# circuit.net
KiCad netlist of a schematic drawn in EAGLE
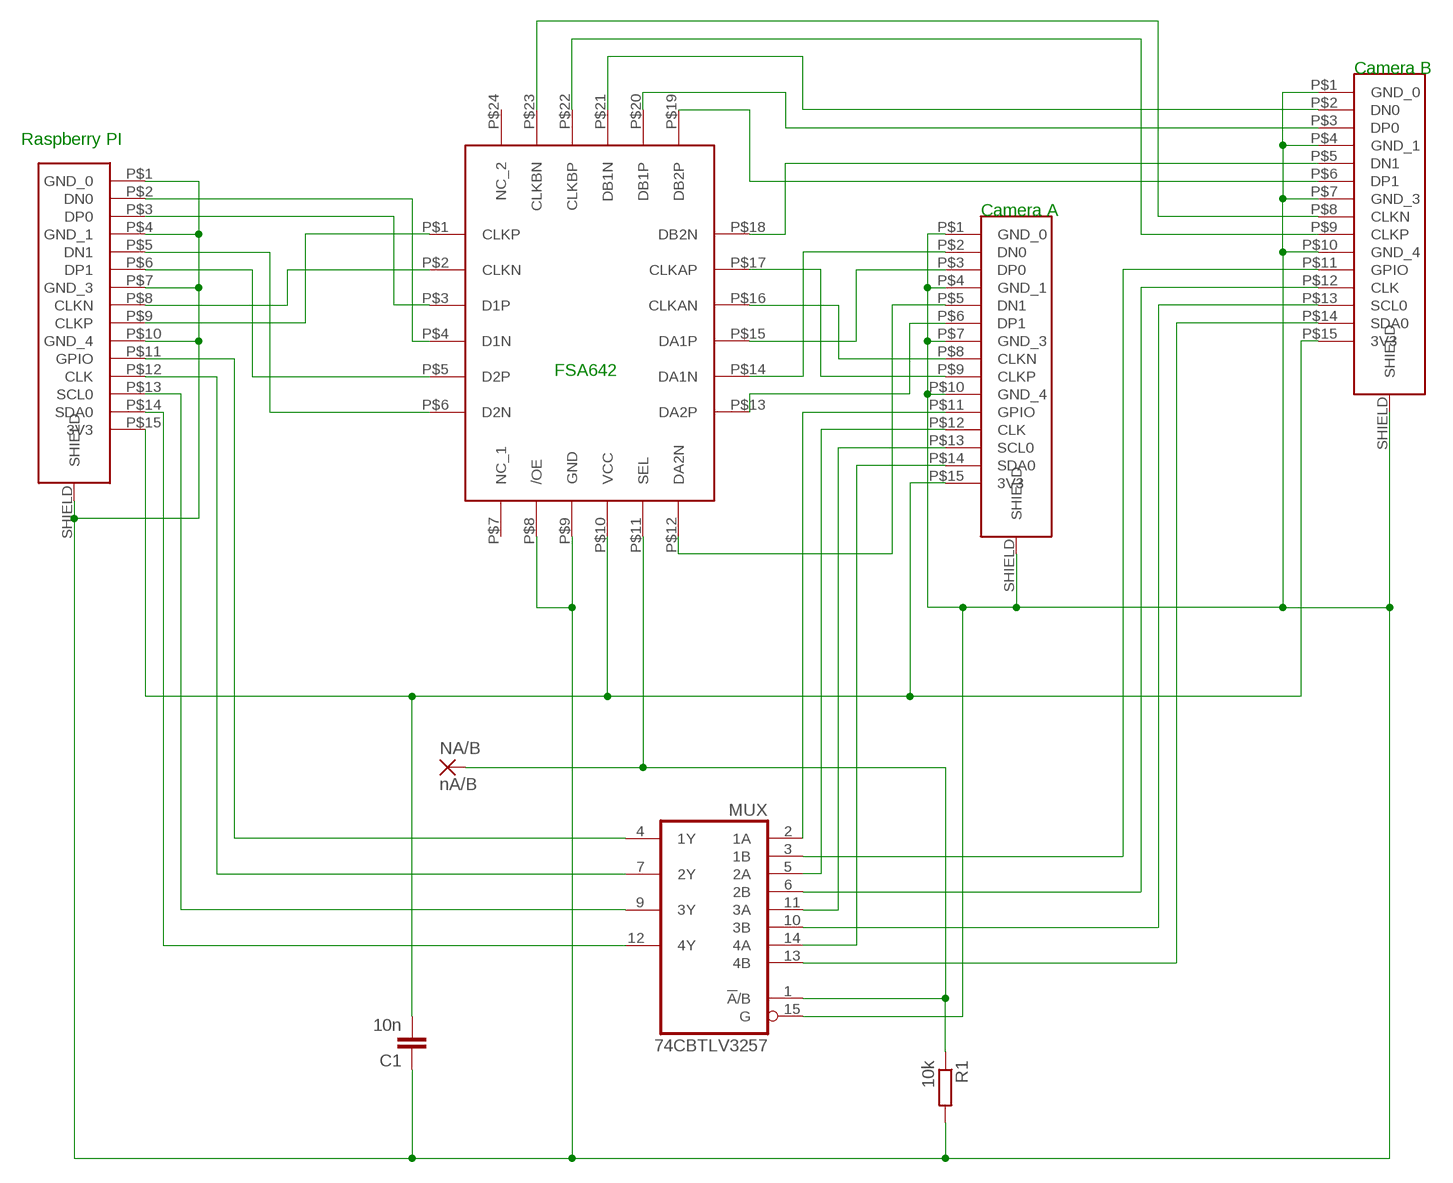
[diagram p0: schematic, sheet 1]

(export (version "E")
  (design (tool "Eeschema 10.0.6"))
  (components
    (comp (ref "C1")
      (value "10n")
      (footprint "eagle-import:C1206")
      (libsource (lib "eagle-import") (part "C-EUC1206"))
    )
    (comp (ref "CAM_A")
      (value "PICAM")
      (footprint "eagle-import:FPC-CONN-15-SMD")
      (libsource (lib "eagle-import") (part "PICAM"))
    )
    (comp (ref "CAM_B")
      (value "PICAM")
      (footprint "eagle-import:FPC-CONN-15-SMD")
      (libsource (lib "eagle-import") (part "PICAM"))
    )
    (comp (ref "MUX")
      (value "74CBTLV3257")
      (footprint "eagle-import:SO16")
      (libsource (lib "eagle-import") (part "74157DHCT"))
    )
    (comp (ref "NA/B")
      (value "nA/B")
      (footprint "eagle-import:SMD1,27-2,54")
      (libsource (lib "eagle-import") (part "SMD2"))
    )
    (comp (ref "R1")
      (value "10k")
      (footprint "eagle-import:R1206")
      (libsource (lib "eagle-import") (part "R-EU_R1206"))
    )
    (comp (ref "RPI")
      (value "PICAM")
      (footprint "eagle-import:FPC-CONN-15-SMD")
      (libsource (lib "eagle-import") (part "PICAM"))
    )
    (comp (ref "U$1")
      (value "FSA642")
      (footprint "eagle-import:UMLP-24")
      (libsource (lib "eagle-import") (part "FSA642"))
    )
  )
  (nets
    (net (code "1") (name "Net-(CAM_A-3V3)") (class "Default")
      (node (ref "C1") (pin "2") (pinfunction "2_2") (pintype "passive"))
      (node (ref "CAM_A") (pin "P$15") (pinfunction "3V3_P$15") (pintype "bidirectional"))
      (node (ref "CAM_B") (pin "P$15") (pinfunction "3V3_P$15") (pintype "bidirectional"))
      (node (ref "RPI") (pin "P$15") (pinfunction "3V3_P$15") (pintype "bidirectional"))
      (node (ref "U$1") (pin "P$10") (pinfunction "VCC_P$10") (pintype "bidirectional"))
    )
    (net (code "2") (name "Net-(CAM_A-CLK)") (class "Default")
      (node (ref "CAM_A") (pin "P$12") (pinfunction "CLK_P$12") (pintype "bidirectional"))
      (node (ref "MUX") (pin "5") (pinfunction "2A_5") (pintype "input"))
    )
    (net (code "3") (name "Net-(CAM_A-CLKN)") (class "Default")
      (node (ref "CAM_A") (pin "P$8") (pinfunction "CLKN_P$8") (pintype "bidirectional"))
      (node (ref "U$1") (pin "P$16") (pinfunction "CLKAN_P$16") (pintype "bidirectional"))
    )
    (net (code "4") (name "Net-(CAM_A-CLKP)") (class "Default")
      (node (ref "CAM_A") (pin "P$9") (pinfunction "CLKP_P$9") (pintype "bidirectional"))
      (node (ref "U$1") (pin "P$17") (pinfunction "CLKAP_P$17") (pintype "bidirectional"))
    )
    (net (code "5") (name "Net-(CAM_A-DN0)") (class "Default")
      (node (ref "CAM_A") (pin "P$2") (pinfunction "DN0_P$2") (pintype "bidirectional"))
      (node (ref "U$1") (pin "P$14") (pinfunction "DA1N_P$14") (pintype "bidirectional"))
    )
    (net (code "6") (name "Net-(CAM_A-DN1)") (class "Default")
      (node (ref "CAM_A") (pin "P$5") (pinfunction "DN1_P$5") (pintype "bidirectional"))
      (node (ref "U$1") (pin "P$12") (pinfunction "DA2N_P$12") (pintype "bidirectional"))
    )
    (net (code "7") (name "Net-(CAM_A-DP0)") (class "Default")
      (node (ref "CAM_A") (pin "P$3") (pinfunction "DP0_P$3") (pintype "bidirectional"))
      (node (ref "U$1") (pin "P$15") (pinfunction "DA1P_P$15") (pintype "bidirectional"))
    )
    (net (code "8") (name "Net-(CAM_A-DP1)") (class "Default")
      (node (ref "CAM_A") (pin "P$6") (pinfunction "DP1_P$6") (pintype "bidirectional"))
      (node (ref "U$1") (pin "P$13") (pinfunction "DA2P_P$13") (pintype "bidirectional"))
    )
    (net (code "9") (name "Net-(CAM_A-GND_0)") (class "Default")
      (node (ref "C1") (pin "1") (pinfunction "1_1") (pintype "passive"))
      (node (ref "CAM_A") (pin "P$1") (pinfunction "GND_0_P$1") (pintype "bidirectional"))
      (node (ref "CAM_A") (pin "P$10") (pinfunction "GND_4_P$10") (pintype "bidirectional"))
      (node (ref "CAM_A") (pin "P$4") (pinfunction "GND_1_P$4") (pintype "bidirectional"))
      (node (ref "CAM_A") (pin "P$7") (pinfunction "GND_3_P$7") (pintype "bidirectional"))
      (node (ref "CAM_A") (pin "SHIELD") (pinfunction "SHIELD_SHIELD") (pintype "bidirectional"))
      (node (ref "CAM_B") (pin "P$1") (pinfunction "GND_0_P$1") (pintype "bidirectional"))
      (node (ref "CAM_B") (pin "P$10") (pinfunction "GND_4_P$10") (pintype "bidirectional"))
      (node (ref "CAM_B") (pin "P$4") (pinfunction "GND_1_P$4") (pintype "bidirectional"))
      (node (ref "CAM_B") (pin "P$7") (pinfunction "GND_3_P$7") (pintype "bidirectional"))
      (node (ref "CAM_B") (pin "SHIELD") (pinfunction "SHIELD_SHIELD") (pintype "bidirectional"))
      (node (ref "MUX") (pin "15") (pinfunction "G_15") (pintype "input"))
      (node (ref "R1") (pin "2") (pinfunction "2_2") (pintype "passive"))
      (node (ref "RPI") (pin "P$1") (pinfunction "GND_0_P$1") (pintype "bidirectional"))
      (node (ref "RPI") (pin "P$10") (pinfunction "GND_4_P$10") (pintype "bidirectional"))
      (node (ref "RPI") (pin "P$4") (pinfunction "GND_1_P$4") (pintype "bidirectional"))
      (node (ref "RPI") (pin "P$7") (pinfunction "GND_3_P$7") (pintype "bidirectional"))
      (node (ref "RPI") (pin "SHIELD") (pinfunction "SHIELD_SHIELD") (pintype "bidirectional"))
      (node (ref "U$1") (pin "P$8") (pinfunction "/OE_P$8") (pintype "bidirectional"))
      (node (ref "U$1") (pin "P$9") (pinfunction "GND_P$9") (pintype "bidirectional"))
    )
    (net (code "10") (name "Net-(CAM_A-GPIO)") (class "Default")
      (node (ref "CAM_A") (pin "P$11") (pinfunction "GPIO_P$11") (pintype "bidirectional"))
      (node (ref "MUX") (pin "2") (pinfunction "1A_2") (pintype "input"))
    )
    (net (code "11") (name "Net-(CAM_A-SCL0)") (class "Default")
      (node (ref "CAM_A") (pin "P$13") (pinfunction "SCL0_P$13") (pintype "bidirectional"))
      (node (ref "MUX") (pin "11") (pinfunction "3A_11") (pintype "input"))
    )
    (net (code "12") (name "Net-(CAM_A-SDA0)") (class "Default")
      (node (ref "CAM_A") (pin "P$14") (pinfunction "SDA0_P$14") (pintype "bidirectional"))
      (node (ref "MUX") (pin "14") (pinfunction "4A_14") (pintype "input"))
    )
    (net (code "13") (name "Net-(CAM_B-CLK)") (class "Default")
      (node (ref "CAM_B") (pin "P$12") (pinfunction "CLK_P$12") (pintype "bidirectional"))
      (node (ref "MUX") (pin "6") (pinfunction "2B_6") (pintype "input"))
    )
    (net (code "14") (name "Net-(CAM_B-CLKN)") (class "Default")
      (node (ref "CAM_B") (pin "P$8") (pinfunction "CLKN_P$8") (pintype "bidirectional"))
      (node (ref "U$1") (pin "P$23") (pinfunction "CLKBN_P$23") (pintype "bidirectional"))
    )
    (net (code "15") (name "Net-(CAM_B-CLKP)") (class "Default")
      (node (ref "CAM_B") (pin "P$9") (pinfunction "CLKP_P$9") (pintype "bidirectional"))
      (node (ref "U$1") (pin "P$22") (pinfunction "CLKBP_P$22") (pintype "bidirectional"))
    )
    (net (code "16") (name "Net-(CAM_B-DN0)") (class "Default")
      (node (ref "CAM_B") (pin "P$2") (pinfunction "DN0_P$2") (pintype "bidirectional"))
      (node (ref "U$1") (pin "P$21") (pinfunction "DB1N_P$21") (pintype "bidirectional"))
    )
    (net (code "17") (name "Net-(CAM_B-DN1)") (class "Default")
      (node (ref "CAM_B") (pin "P$5") (pinfunction "DN1_P$5") (pintype "bidirectional"))
      (node (ref "U$1") (pin "P$18") (pinfunction "DB2N_P$18") (pintype "bidirectional"))
    )
    (net (code "18") (name "Net-(CAM_B-DP0)") (class "Default")
      (node (ref "CAM_B") (pin "P$3") (pinfunction "DP0_P$3") (pintype "bidirectional"))
      (node (ref "U$1") (pin "P$20") (pinfunction "DB1P_P$20") (pintype "bidirectional"))
    )
    (net (code "19") (name "Net-(CAM_B-DP1)") (class "Default")
      (node (ref "CAM_B") (pin "P$6") (pinfunction "DP1_P$6") (pintype "bidirectional"))
      (node (ref "U$1") (pin "P$19") (pinfunction "DB2P_P$19") (pintype "bidirectional"))
    )
    (net (code "20") (name "Net-(CAM_B-GPIO)") (class "Default")
      (node (ref "CAM_B") (pin "P$11") (pinfunction "GPIO_P$11") (pintype "bidirectional"))
      (node (ref "MUX") (pin "3") (pinfunction "1B_3") (pintype "input"))
    )
    (net (code "21") (name "Net-(CAM_B-SCL0)") (class "Default")
      (node (ref "CAM_B") (pin "P$13") (pinfunction "SCL0_P$13") (pintype "bidirectional"))
      (node (ref "MUX") (pin "10") (pinfunction "3B_10") (pintype "input"))
    )
    (net (code "22") (name "Net-(CAM_B-SDA0)") (class "Default")
      (node (ref "CAM_B") (pin "P$14") (pinfunction "SDA0_P$14") (pintype "bidirectional"))
      (node (ref "MUX") (pin "13") (pinfunction "4B_13") (pintype "input"))
    )
    (net (code "23") (name "Net-(MUXA-1Y)") (class "Default")
      (node (ref "MUX") (pin "4") (pinfunction "1Y_4") (pintype "output"))
      (node (ref "RPI") (pin "P$11") (pinfunction "GPIO_P$11") (pintype "bidirectional"))
    )
    (net (code "24") (name "Net-(MUXA-2Y)") (class "Default")
      (node (ref "MUX") (pin "7") (pinfunction "2Y_7") (pintype "output"))
      (node (ref "RPI") (pin "P$12") (pinfunction "CLK_P$12") (pintype "bidirectional"))
    )
    (net (code "25") (name "Net-(MUXA-3Y)") (class "Default")
      (node (ref "MUX") (pin "9") (pinfunction "3Y_9") (pintype "output"))
      (node (ref "RPI") (pin "P$13") (pinfunction "SCL0_P$13") (pintype "bidirectional"))
    )
    (net (code "26") (name "Net-(MUXA-4Y)") (class "Default")
      (node (ref "MUX") (pin "12") (pinfunction "4Y_12") (pintype "output"))
      (node (ref "RPI") (pin "P$14") (pinfunction "SDA0_P$14") (pintype "bidirectional"))
    )
    (net (code "27") (name "Net-(MUXA-~{A}{slash}B)") (class "Default")
      (node (ref "MUX") (pin "1") (pinfunction "~{A}/B_1") (pintype "input"))
      (node (ref "NA/B") (pin "1") (pinfunction "P_1") (pintype "passive"))
      (node (ref "R1") (pin "1") (pinfunction "1_1") (pintype "passive"))
      (node (ref "U$1") (pin "P$11") (pinfunction "SEL_P$11") (pintype "bidirectional"))
    )
    (net (code "28") (name "Net-(RPI-CLKN)") (class "Default")
      (node (ref "RPI") (pin "P$8") (pinfunction "CLKN_P$8") (pintype "bidirectional"))
      (node (ref "U$1") (pin "P$2") (pinfunction "CLKN_P$2") (pintype "bidirectional"))
    )
    (net (code "29") (name "Net-(RPI-CLKP)") (class "Default")
      (node (ref "RPI") (pin "P$9") (pinfunction "CLKP_P$9") (pintype "bidirectional"))
      (node (ref "U$1") (pin "P$1") (pinfunction "CLKP_P$1") (pintype "bidirectional"))
    )
    (net (code "30") (name "Net-(RPI-DN0)") (class "Default")
      (node (ref "RPI") (pin "P$2") (pinfunction "DN0_P$2") (pintype "bidirectional"))
      (node (ref "U$1") (pin "P$4") (pinfunction "D1N_P$4") (pintype "bidirectional"))
    )
    (net (code "31") (name "Net-(RPI-DN1)") (class "Default")
      (node (ref "RPI") (pin "P$5") (pinfunction "DN1_P$5") (pintype "bidirectional"))
      (node (ref "U$1") (pin "P$6") (pinfunction "D2N_P$6") (pintype "bidirectional"))
    )
    (net (code "32") (name "Net-(RPI-DP0)") (class "Default")
      (node (ref "RPI") (pin "P$3") (pinfunction "DP0_P$3") (pintype "bidirectional"))
      (node (ref "U$1") (pin "P$3") (pinfunction "D1P_P$3") (pintype "bidirectional"))
    )
    (net (code "33") (name "Net-(RPI-DP1)") (class "Default")
      (node (ref "RPI") (pin "P$6") (pinfunction "DP1_P$6") (pintype "bidirectional"))
      (node (ref "U$1") (pin "P$5") (pinfunction "D2P_P$5") (pintype "bidirectional"))
    )
    (net (code "34") (name "unconnected-(U$1-NC_1-PadP$7)") (class "Default")
      (node (ref "U$1") (pin "P$7") (pinfunction "NC_1_P$7") (pintype "bidirectional"))
    )
    (net (code "35") (name "unconnected-(U$1-NC_2-PadP$24)") (class "Default")
      (node (ref "U$1") (pin "P$24") (pinfunction "NC_2_P$24") (pintype "bidirectional"))
    )
  )
)
